# Canzasi-Prot.net
KiCad netlist of a schematic drawn in EAGLE
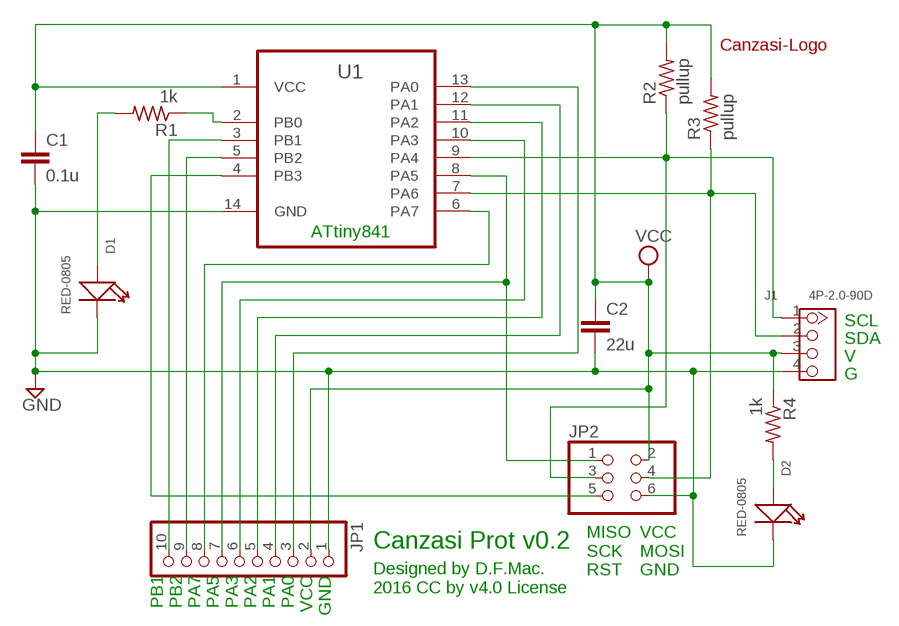
[diagram p0: schematic, sheet 1]

(export (version "E")
  (design (tool "Eeschema 10.0.6"))
  (components
    (comp (ref "C1")
      (value "0.1u")
      (footprint "eagle-import:C0603")
      (libsource (lib "eagle-import") (part "C-EUC0603"))
    )
    (comp (ref "C2")
      (value "22u")
      (footprint "eagle-import:C0805")
      (libsource (lib "eagle-import") (part "C-EUC0805"))
    )
    (comp (ref "D1")
      (value "RED-0805")
      (footprint "eagle-import:LED-0805")
      (fields (field (name "MPN") "17-215SURC/S530-A2/TR8"))
      (libsource (lib "eagle-import") (part "SMD-LED-CLEAR-RED(0805)"))
    )
    (comp (ref "D2")
      (value "RED-0805")
      (footprint "eagle-import:LED-0805")
      (fields (field (name "MPN") "17-215SURC/S530-A2/TR8"))
      (libsource (lib "eagle-import") (part "SMD-LED-CLEAR-RED(0805)"))
    )
    (comp (ref "J1")
      (value "4P-2.0-90D")
      (footprint "eagle-import:HW4-2.0-90D")
      (libsource (lib "eagle-import") (part "GROVE-CONNECTOR-DIP-90D(4P-2.0)"))
    )
    (comp (ref "JP1")
      (value "PINHD-1X10")
      (footprint "eagle-import:1X10")
      (libsource (lib "eagle-import") (part "PINHD-1X10"))
    )
    (comp (ref "JP2")
      (value "PINHD-2X3")
      (footprint "eagle-import:2X03")
      (libsource (lib "eagle-import") (part "PINHD-2X3"))
    )
    (comp (ref "R1")
      (value "1k")
      (footprint "eagle-import:R0603")
      (libsource (lib "eagle-import") (part "R-US_R0603"))
    )
    (comp (ref "R2")
      (value "pullup")
      (footprint "eagle-import:R0603")
      (libsource (lib "eagle-import") (part "R-US_R0603"))
    )
    (comp (ref "R3")
      (value "pullup")
      (footprint "eagle-import:R0603")
      (libsource (lib "eagle-import") (part "R-US_R0603"))
    )
    (comp (ref "R4")
      (value "1k")
      (footprint "eagle-import:R0603")
      (libsource (lib "eagle-import") (part "R-US_R0603"))
    )
    (comp (ref "U$1")
      (value "CANZASI-LOGOMEDIUM")
      (footprint "eagle-import:CANZASI-LOGO-MEDIUM")
      (libsource (lib "eagle-import") (part "CANZASI-LOGOMEDIUM"))
    )
    (comp (ref "U1")
      (value "ATTINY44A-SSU")
      (footprint "eagle-import:SOIC127P600X175-14N")
      (libsource (lib "eagle-import") (part "ATTINY44A-SSU"))
    )
  )
  (nets
    (net (code "1") (name "GND") (class "Default")
      (node (ref "C1") (pin "2") (pinfunction "2_2") (pintype "passive"))
      (node (ref "C2") (pin "2") (pinfunction "2_2") (pintype "passive"))
      (node (ref "D1") (pin "-") (pinfunction "-_-") (pintype "passive"))
      (node (ref "D2") (pin "-") (pinfunction "-_-") (pintype "passive"))
      (node (ref "J1") (pin "4") (pinfunction "4_4") (pintype "bidirectional"))
      (node (ref "JP1") (pin "1") (pinfunction "1_1") (pintype "passive"))
      (node (ref "JP2") (pin "6") (pinfunction "6_6") (pintype "passive"))
      (node (ref "U1") (pin "14") (pinfunction "GND_14") (pintype "power_in"))
    )
    (net (code "2") (name "Net-(D1-Pad+)") (class "Default")
      (node (ref "D1") (pin "+") (pinfunction "+_+") (pintype "passive"))
      (node (ref "R1") (pin "2") (pinfunction "2_2") (pintype "passive"))
    )
    (net (code "3") (name "Net-(D2-Pad+)") (class "Default")
      (node (ref "D2") (pin "+") (pinfunction "+_+") (pintype "passive"))
      (node (ref "R4") (pin "2") (pinfunction "2_2") (pintype "passive"))
    )
    (net (code "4") (name "Net-(U1-PA0)") (class "Default")
      (node (ref "JP1") (pin "3") (pinfunction "3_3") (pintype "passive"))
      (node (ref "U1") (pin "13") (pinfunction "PA0_13") (pintype "bidirectional"))
    )
    (net (code "5") (name "Net-(U1-PA1)") (class "Default")
      (node (ref "JP1") (pin "4") (pinfunction "4_4") (pintype "passive"))
      (node (ref "U1") (pin "12") (pinfunction "PA1_12") (pintype "bidirectional"))
    )
    (net (code "6") (name "Net-(U1-PA2)") (class "Default")
      (node (ref "JP1") (pin "5") (pinfunction "5_5") (pintype "passive"))
      (node (ref "U1") (pin "11") (pinfunction "PA2_11") (pintype "bidirectional"))
    )
    (net (code "7") (name "Net-(U1-PA3)") (class "Default")
      (node (ref "JP1") (pin "6") (pinfunction "6_6") (pintype "passive"))
      (node (ref "U1") (pin "10") (pinfunction "PA3_10") (pintype "bidirectional"))
    )
    (net (code "8") (name "Net-(U1-PA4)") (class "Default")
      (node (ref "J1") (pin "1") (pinfunction "1_1") (pintype "bidirectional"))
      (node (ref "JP2") (pin "3") (pinfunction "3_3") (pintype "passive"))
      (node (ref "R2") (pin "1") (pinfunction "1_1") (pintype "passive"))
      (node (ref "U1") (pin "9") (pinfunction "PA4_9") (pintype "bidirectional"))
    )
    (net (code "9") (name "Net-(U1-PA5)") (class "Default")
      (node (ref "JP1") (pin "7") (pinfunction "7_7") (pintype "passive"))
      (node (ref "JP2") (pin "1") (pinfunction "1_1") (pintype "passive"))
      (node (ref "U1") (pin "8") (pinfunction "PA5_8") (pintype "bidirectional"))
    )
    (net (code "10") (name "Net-(U1-PA6)") (class "Default")
      (node (ref "J1") (pin "2") (pinfunction "2_2") (pintype "bidirectional"))
      (node (ref "JP2") (pin "4") (pinfunction "4_4") (pintype "passive"))
      (node (ref "R3") (pin "1") (pinfunction "1_1") (pintype "passive"))
      (node (ref "U1") (pin "7") (pinfunction "PA6_7") (pintype "bidirectional"))
    )
    (net (code "11") (name "Net-(U1-PA7)") (class "Default")
      (node (ref "JP1") (pin "8") (pinfunction "8_8") (pintype "passive"))
      (node (ref "U1") (pin "6") (pinfunction "PA7_6") (pintype "bidirectional"))
    )
    (net (code "12") (name "Net-(U1-PB0)") (class "Default")
      (node (ref "R1") (pin "1") (pinfunction "1_1") (pintype "passive"))
      (node (ref "U1") (pin "2") (pinfunction "PB0_2") (pintype "bidirectional"))
    )
    (net (code "13") (name "Net-(U1-PB1)") (class "Default")
      (node (ref "JP1") (pin "10") (pinfunction "10_10") (pintype "passive"))
      (node (ref "U1") (pin "3") (pinfunction "PB1_3") (pintype "bidirectional"))
    )
    (net (code "14") (name "Net-(U1-PB2)") (class "Default")
      (node (ref "JP1") (pin "9") (pinfunction "9_9") (pintype "passive"))
      (node (ref "U1") (pin "5") (pinfunction "PB2_5") (pintype "bidirectional"))
    )
    (net (code "15") (name "Net-(U1-PB3)") (class "Default")
      (node (ref "JP2") (pin "5") (pinfunction "5_5") (pintype "passive"))
      (node (ref "U1") (pin "4") (pinfunction "PB3_4") (pintype "bidirectional"))
    )
    (net (code "16") (name "VCC") (class "Default")
      (node (ref "C1") (pin "1") (pinfunction "1_1") (pintype "passive"))
      (node (ref "C2") (pin "1") (pinfunction "1_1") (pintype "passive"))
      (node (ref "J1") (pin "3") (pinfunction "3_3") (pintype "bidirectional"))
      (node (ref "JP1") (pin "2") (pinfunction "2_2") (pintype "passive"))
      (node (ref "JP2") (pin "2") (pinfunction "2_2") (pintype "passive"))
      (node (ref "R2") (pin "2") (pinfunction "2_2") (pintype "passive"))
      (node (ref "R3") (pin "2") (pinfunction "2_2") (pintype "passive"))
      (node (ref "R4") (pin "1") (pinfunction "1_1") (pintype "passive"))
      (node (ref "U1") (pin "1") (pinfunction "VCC_1") (pintype "power_in"))
    )
  )
)
